# Sheet_1_2021-12-04.net
KiCad netlist of a schematic drawn in Altium Designer
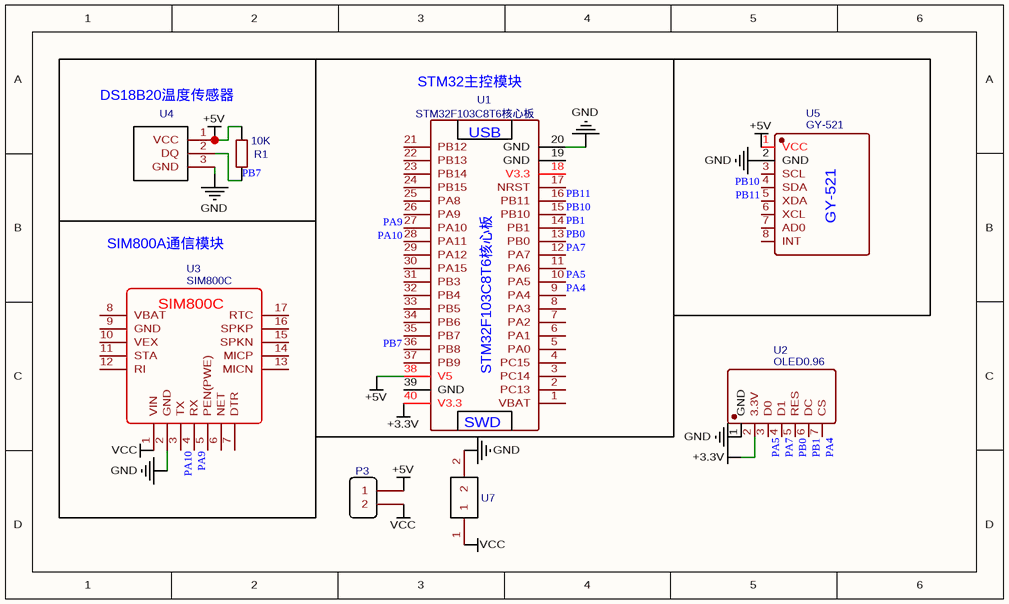
[diagram p0: Sheet_1_2021-12-04.schdoc]

(export (version "E")
  (design (tool "Eeschema 10.0.6"))
  (components
    (comp (ref "P3")
      (value "2.54-1*2P_ZX")
      (fields (field (name "BOM_SUPPLIER PART") "C115245"))
      (libsource (lib "altium-import") (part "root_0_2.54-1*2P_ZX_"))
    )
    (comp (ref "R1")
      (value "10K")
      (fields
        (field (name "BOM_SUPPLIER PART") "C120226")
        (field (name "BOM_MANUFACTURER PART") "CF1/2W-330Ω±5% T52")
        (field (name "TOLERANCE") "±5%")
      )
      (libsource (lib "altium-import") (part "root_1_10K_"))
    )
    (comp (ref "U1")
      (value "STM32F103C8T6核心板")
      (fields
        (field (name "BOM_SUPPLIER PART") "C8734")
        (field (name "BOM_MANUFACTURER PART") "STM32F103C8T6最小系统模块")
        (field (name "SUBPART_NO") "1")
        (field (name "CONTRIBUTOR") "Kolin")
      )
      (libsource (lib "altium-import") (part "root_2_STM32F103C8T6核心板_"))
    )
    (comp (ref "U2")
      (value "OLED0.96")
      (fields (field (name "CONTRIBUTOR") "simple_ji"))
      (libsource (lib "altium-import") (part "root_1_OLED0.96_"))
    )
    (comp (ref "U3")
      (value "SIM800C")
      (fields (field (name "CONTRIBUTOR") "18317631082"))
      (libsource (lib "altium-import") (part "root_0_SIM800C_"))
    )
    (comp (ref "U4")
      (value "DS18B20（防水版）")
      (fields (field (name "CONTRIBUTOR") "Bird"))
      (libsource (lib "altium-import") (part "root_0_DS18B20（防水版）_"))
    )
    (comp (ref "U5")
      (value "GY-521")
      (fields (field (name "CONTRIBUTOR") "maoMaoLan"))
      (libsource (lib "altium-import") (part "root_0_GY-521_"))
    )
    (comp (ref "U7")
      (value "双排针2×1P")
      (fields (field (name "CONTRIBUTOR") "sibing2020"))
      (libsource (lib "altium-import") (part "root_1_双排针2×1P_"))
    )
  )
  (nets
    (net (code "1") (name "+3.3V") (class "Default")
      (node (ref "U1") (pin "40") (pinfunction "V3.3_40") (pintype "passive"))
      (node (ref "U2") (pin "2") (pinfunction "3.3V_2") (pintype "passive"))
    )
    (net (code "2") (name "+5V") (class "Default")
      (node (ref "P3") (pin "1") (pinfunction "1_1") (pintype "passive"))
      (node (ref "R1") (pin "2") (pinfunction "2_2") (pintype "passive"))
      (node (ref "U1") (pin "38") (pinfunction "V5_38") (pintype "passive"))
      (node (ref "U4") (pin "1") (pinfunction "VCC_1") (pintype "passive"))
      (node (ref "U5") (pin "1") (pinfunction "VCC_1") (pintype "passive"))
    )
    (net (code "3") (name "/PA4") (class "Default")
      (node (ref "U1") (pin "9") (pinfunction "PA4_9") (pintype "passive"))
      (node (ref "U2") (pin "7") (pinfunction "CS_7") (pintype "passive"))
    )
    (net (code "4") (name "/PA5") (class "Default")
      (node (ref "U1") (pin "10") (pinfunction "PA5_10") (pintype "passive"))
      (node (ref "U2") (pin "3") (pinfunction "D0_3") (pintype "passive"))
    )
    (net (code "5") (name "/PA7") (class "Default")
      (node (ref "U1") (pin "12") (pinfunction "PA7_12") (pintype "passive"))
      (node (ref "U2") (pin "4") (pinfunction "D1_4") (pintype "passive"))
    )
    (net (code "6") (name "/PA9") (class "Default")
      (node (ref "U1") (pin "26") (pinfunction "PA9_26") (pintype "passive"))
      (node (ref "U3") (pin "4") (pinfunction "RX_4") (pintype "passive"))
    )
    (net (code "7") (name "/PA10") (class "Default")
      (node (ref "U1") (pin "27") (pinfunction "PA10_27") (pintype "passive"))
      (node (ref "U3") (pin "3") (pinfunction "TX_3") (pintype "passive"))
    )
    (net (code "8") (name "/PB0") (class "Default")
      (node (ref "U1") (pin "13") (pinfunction "PB0_13") (pintype "passive"))
      (node (ref "U2") (pin "5") (pinfunction "RES_5") (pintype "passive"))
    )
    (net (code "9") (name "/PB1") (class "Default")
      (node (ref "U1") (pin "14") (pinfunction "PB1_14") (pintype "passive"))
      (node (ref "U2") (pin "6") (pinfunction "DC_6") (pintype "passive"))
    )
    (net (code "10") (name "/PB7") (class "Default")
      (node (ref "R1") (pin "1") (pinfunction "1_1") (pintype "passive"))
      (node (ref "U1") (pin "35") (pinfunction "PB7_35") (pintype "passive"))
      (node (ref "U4") (pin "2") (pinfunction "DQ_2") (pintype "passive"))
    )
    (net (code "11") (name "/PB10") (class "Default")
      (node (ref "U1") (pin "15") (pinfunction "PB10_15") (pintype "passive"))
      (node (ref "U5") (pin "3") (pinfunction "SCL_3") (pintype "passive"))
    )
    (net (code "12") (name "/PB11") (class "Default")
      (node (ref "U1") (pin "16") (pinfunction "PB11_16") (pintype "passive"))
      (node (ref "U5") (pin "4") (pinfunction "SDA_4") (pintype "passive"))
    )
    (net (code "13") (name "GND") (class "Default")
      (node (ref "U1") (pin "20") (pinfunction "GND_20") (pintype "passive"))
      (node (ref "U2") (pin "1") (pinfunction "GND_1") (pintype "passive"))
      (node (ref "U3") (pin "2") (pinfunction "GND_2") (pintype "passive"))
      (node (ref "U4") (pin "3") (pinfunction "GND_3") (pintype "passive"))
      (node (ref "U5") (pin "2") (pinfunction "GND_2") (pintype "passive"))
      (node (ref "U7") (pin "2") (pinfunction "2_2") (pintype "passive"))
    )
    (net (code "14") (name "VCC") (class "Default")
      (node (ref "P3") (pin "2") (pinfunction "2_2") (pintype "passive"))
      (node (ref "U3") (pin "1") (pinfunction "VIN_1") (pintype "passive"))
      (node (ref "U7") (pin "1") (pinfunction "1_1") (pintype "passive"))
    )
    (net (code "15") (name "unconnected-(U1-GND-Pad19)") (class "Default")
      (node (ref "U1") (pin "19") (pinfunction "GND_19") (pintype "passive"))
    )
    (net (code "16") (name "unconnected-(U1-GND-Pad39)") (class "Default")
      (node (ref "U1") (pin "39") (pinfunction "GND_39") (pintype "passive"))
    )
    (net (code "17") (name "unconnected-(U1-NRST-Pad17)") (class "Default")
      (node (ref "U1") (pin "17") (pinfunction "NRST_17") (pintype "passive"))
    )
    (net (code "18") (name "unconnected-(U1-PA0-Pad5)") (class "Default")
      (node (ref "U1") (pin "5") (pinfunction "PA0_5") (pintype "passive"))
    )
    (net (code "19") (name "unconnected-(U1-PA1-Pad6)") (class "Default")
      (node (ref "U1") (pin "6") (pinfunction "PA1_6") (pintype "passive"))
    )
    (net (code "20") (name "unconnected-(U1-PA2-Pad7)") (class "Default")
      (node (ref "U1") (pin "7") (pinfunction "PA2_7") (pintype "passive"))
    )
    (net (code "21") (name "unconnected-(U1-PA3-Pad8)") (class "Default")
      (node (ref "U1") (pin "8") (pinfunction "PA3_8") (pintype "passive"))
    )
    (net (code "22") (name "unconnected-(U1-PA6-Pad11)") (class "Default")
      (node (ref "U1") (pin "11") (pinfunction "PA6_11") (pintype "passive"))
    )
    (net (code "23") (name "unconnected-(U1-PA8-Pad25)") (class "Default")
      (node (ref "U1") (pin "25") (pinfunction "PA8_25") (pintype "passive"))
    )
    (net (code "24") (name "unconnected-(U1-PA11-Pad28)") (class "Default")
      (node (ref "U1") (pin "28") (pinfunction "PA11_28") (pintype "passive"))
    )
    (net (code "25") (name "unconnected-(U1-PA12-Pad29)") (class "Default")
      (node (ref "U1") (pin "29") (pinfunction "PA12_29") (pintype "passive"))
    )
    (net (code "26") (name "unconnected-(U1-PA15-Pad30)") (class "Default")
      (node (ref "U1") (pin "30") (pinfunction "PA15_30") (pintype "passive"))
    )
    (net (code "27") (name "unconnected-(U1-PB3-Pad31)") (class "Default")
      (node (ref "U1") (pin "31") (pinfunction "PB3_31") (pintype "passive"))
    )
    (net (code "28") (name "unconnected-(U1-PB4-Pad32)") (class "Default")
      (node (ref "U1") (pin "32") (pinfunction "PB4_32") (pintype "passive"))
    )
    (net (code "29") (name "unconnected-(U1-PB5-Pad33)") (class "Default")
      (node (ref "U1") (pin "33") (pinfunction "PB5_33") (pintype "passive"))
    )
    (net (code "30") (name "unconnected-(U1-PB6-Pad34)") (class "Default")
      (node (ref "U1") (pin "34") (pinfunction "PB6_34") (pintype "passive"))
    )
    (net (code "31") (name "unconnected-(U1-PB8-Pad36)") (class "Default")
      (node (ref "U1") (pin "36") (pinfunction "PB8_36") (pintype "passive"))
    )
    (net (code "32") (name "unconnected-(U1-PB9-Pad37)") (class "Default")
      (node (ref "U1") (pin "37") (pinfunction "PB9_37") (pintype "passive"))
    )
    (net (code "33") (name "unconnected-(U1-PB12-Pad21)") (class "Default")
      (node (ref "U1") (pin "21") (pinfunction "PB12_21") (pintype "passive"))
    )
    (net (code "34") (name "unconnected-(U1-PB13-Pad22)") (class "Default")
      (node (ref "U1") (pin "22") (pinfunction "PB13_22") (pintype "passive"))
    )
    (net (code "35") (name "unconnected-(U1-PB14-Pad23)") (class "Default")
      (node (ref "U1") (pin "23") (pinfunction "PB14_23") (pintype "passive"))
    )
    (net (code "36") (name "unconnected-(U1-PB15-Pad24)") (class "Default")
      (node (ref "U1") (pin "24") (pinfunction "PB15_24") (pintype "passive"))
    )
    (net (code "37") (name "unconnected-(U1-PC13-Pad2)") (class "Default")
      (node (ref "U1") (pin "2") (pinfunction "PC13_2") (pintype "passive"))
    )
    (net (code "38") (name "unconnected-(U1-PC14-Pad3)") (class "Default")
      (node (ref "U1") (pin "3") (pinfunction "PC14_3") (pintype "passive"))
    )
    (net (code "39") (name "unconnected-(U1-PC15-Pad4)") (class "Default")
      (node (ref "U1") (pin "4") (pinfunction "PC15_4") (pintype "passive"))
    )
    (net (code "40") (name "unconnected-(U1-V3.3-Pad18)") (class "Default")
      (node (ref "U1") (pin "18") (pinfunction "V3.3_18") (pintype "passive"))
    )
    (net (code "41") (name "unconnected-(U1-VBAT-Pad1)") (class "Default")
      (node (ref "U1") (pin "1") (pinfunction "VBAT_1") (pintype "passive"))
    )
    (net (code "42") (name "unconnected-(U3-DTR-Pad7)") (class "Default")
      (node (ref "U3") (pin "7") (pinfunction "DTR_7") (pintype "passive"))
    )
    (net (code "43") (name "unconnected-(U3-GND-Pad9)") (class "Default")
      (node (ref "U3") (pin "9") (pinfunction "GND_9") (pintype "passive"))
    )
    (net (code "44") (name "unconnected-(U3-MICN-Pad13)") (class "Default")
      (node (ref "U3") (pin "13") (pinfunction "MICN_13") (pintype "passive"))
    )
    (net (code "45") (name "unconnected-(U3-MICP-Pad14)") (class "Default")
      (node (ref "U3") (pin "14") (pinfunction "MICP_14") (pintype "passive"))
    )
    (net (code "46") (name "unconnected-(U3-NET-Pad6)") (class "Default")
      (node (ref "U3") (pin "6") (pinfunction "NET_6") (pintype "passive"))
    )
    (net (code "47") (name "unconnected-(U3-PEN(PWE)-Pad5)") (class "Default")
      (node (ref "U3") (pin "5") (pinfunction "PEN(PWE)_5") (pintype "passive"))
    )
    (net (code "48") (name "unconnected-(U3-RI-Pad12)") (class "Default")
      (node (ref "U3") (pin "12") (pinfunction "RI_12") (pintype "passive"))
    )
    (net (code "49") (name "unconnected-(U3-RTC-Pad17)") (class "Default")
      (node (ref "U3") (pin "17") (pinfunction "RTC_17") (pintype "passive"))
    )
    (net (code "50") (name "unconnected-(U3-SPKN-Pad15)") (class "Default")
      (node (ref "U3") (pin "15") (pinfunction "SPKN_15") (pintype "passive"))
    )
    (net (code "51") (name "unconnected-(U3-SPKP-Pad16)") (class "Default")
      (node (ref "U3") (pin "16") (pinfunction "SPKP_16") (pintype "passive"))
    )
    (net (code "52") (name "unconnected-(U3-STA-Pad11)") (class "Default")
      (node (ref "U3") (pin "11") (pinfunction "STA_11") (pintype "passive"))
    )
    (net (code "53") (name "unconnected-(U3-VBAT-Pad8)") (class "Default")
      (node (ref "U3") (pin "8") (pinfunction "VBAT_8") (pintype "passive"))
    )
    (net (code "54") (name "unconnected-(U3-VEX-Pad10)") (class "Default")
      (node (ref "U3") (pin "10") (pinfunction "VEX_10") (pintype "passive"))
    )
    (net (code "55") (name "unconnected-(U5-AD0-Pad7)") (class "Default")
      (node (ref "U5") (pin "7") (pinfunction "AD0_7") (pintype "passive"))
    )
    (net (code "56") (name "unconnected-(U5-INT-Pad8)") (class "Default")
      (node (ref "U5") (pin "8") (pinfunction "INT_8") (pintype "passive"))
    )
    (net (code "57") (name "unconnected-(U5-XCL-Pad6)") (class "Default")
      (node (ref "U5") (pin "6") (pinfunction "XCL_6") (pintype "passive"))
    )
    (net (code "58") (name "unconnected-(U5-XDA-Pad5)") (class "Default")
      (node (ref "U5") (pin "5") (pinfunction "XDA_5") (pintype "passive"))
    )
  )
)
